# T-11_Version_1_1.net
KiCad netlist of a schematic drawn in EAGLE
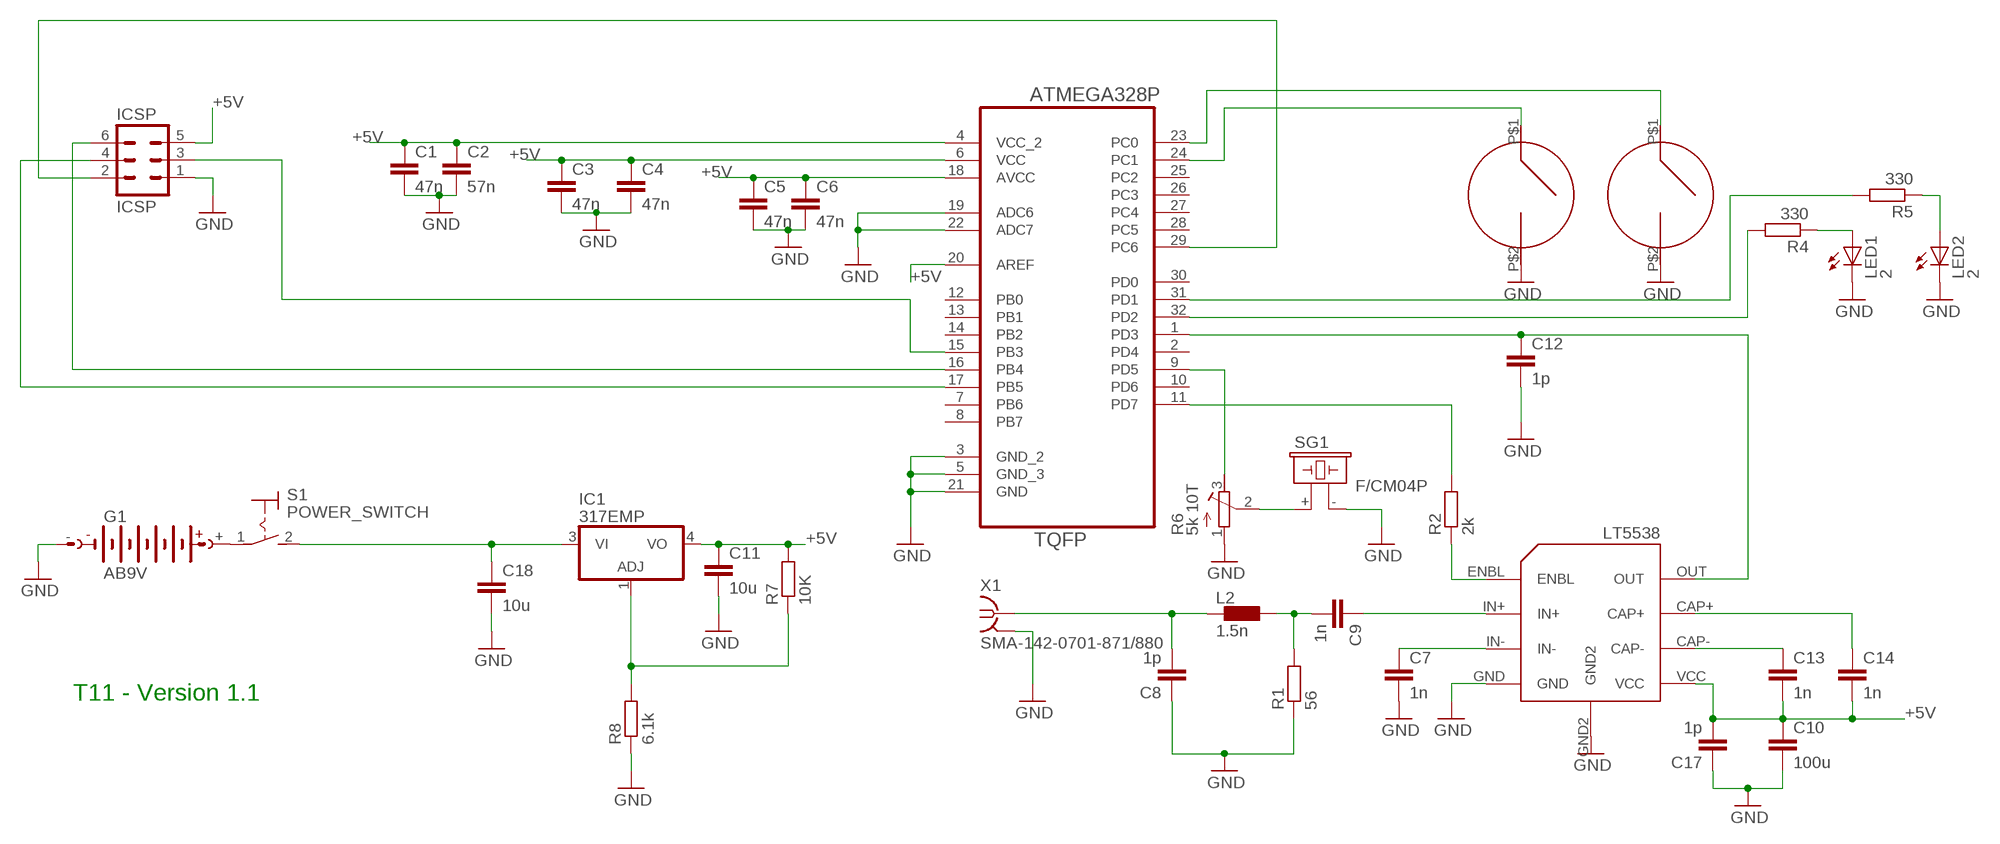
[diagram p0: schematic, sheet 1]

(export (version "E")
  (design (tool "Eeschema 10.0.6"))
  (components
    (comp (ref "C1")
      (value "47n")
      (footprint "eagle-import:C4532")
      (libsource (lib "eagle-import") (part "CC4532"))
    )
    (comp (ref "C2")
      (value "57n")
      (footprint "eagle-import:C4532")
      (libsource (lib "eagle-import") (part "CC4532"))
    )
    (comp (ref "C3")
      (value "47n")
      (footprint "eagle-import:C4532")
      (libsource (lib "eagle-import") (part "CC4532"))
    )
    (comp (ref "C4")
      (value "47n")
      (footprint "eagle-import:C4532")
      (libsource (lib "eagle-import") (part "CC4532"))
    )
    (comp (ref "C5")
      (value "47n")
      (footprint "eagle-import:C4532")
      (libsource (lib "eagle-import") (part "CC4532"))
    )
    (comp (ref "C6")
      (value "47n")
      (footprint "eagle-import:C4532")
      (libsource (lib "eagle-import") (part "CC4532"))
    )
    (comp (ref "C7")
      (value "1n")
      (footprint "eagle-import:C4532")
      (libsource (lib "eagle-import") (part "CC4532"))
    )
    (comp (ref "C8")
      (value "1p")
      (footprint "eagle-import:C4532")
      (libsource (lib "eagle-import") (part "CC4532"))
    )
    (comp (ref "C9")
      (value "1n")
      (footprint "eagle-import:C4532")
      (libsource (lib "eagle-import") (part "CC4532"))
    )
    (comp (ref "C10")
      (value "100u")
      (footprint "eagle-import:C4532")
      (libsource (lib "eagle-import") (part "CC4532"))
    )
    (comp (ref "C11")
      (value "10u")
      (footprint "eagle-import:C4532")
      (libsource (lib "eagle-import") (part "CC4532"))
    )
    (comp (ref "C12")
      (value "1p")
      (footprint "eagle-import:C0805")
      (fields (field (name "SPICEMODEL") "1p"))
      (libsource (lib "eagle-import") (part "C"))
    )
    (comp (ref "C13")
      (value "1n")
      (footprint "eagle-import:C4532")
      (libsource (lib "eagle-import") (part "CC4532"))
    )
    (comp (ref "C14")
      (value "1n")
      (footprint "eagle-import:C4532")
      (libsource (lib "eagle-import") (part "CC4532"))
    )
    (comp (ref "C17")
      (value "1p")
      (footprint "eagle-import:C4532")
      (libsource (lib "eagle-import") (part "CC4532"))
    )
    (comp (ref "C18")
      (value "10u")
      (footprint "eagle-import:C4532")
      (libsource (lib "eagle-import") (part "CC4532"))
    )
    (comp (ref "G1")
      (value "AB9V")
      (footprint "eagle-import:AB9V")
      (libsource (lib "eagle-import") (part "AB9V"))
    )
    (comp (ref "IC1")
      (value "317EMP")
      (footprint "eagle-import:SOT223")
      (libsource (lib "eagle-import") (part "317EMP"))
    )
    (comp (ref "ICSP")
      (value "ICSP")
      (footprint "eagle-import:MA03-2")
      (libsource (lib "eagle-import") (part "MA03-2"))
    )
    (comp (ref "L2")
      (value "1.5n")
      (footprint "eagle-import:L4532P")
      (libsource (lib "eagle-import") (part "LL4532P"))
    )
    (comp (ref "LED1")
      (value "2")
      (footprint "eagle-import:LED3MM")
      (libsource (lib "eagle-import") (part "LED3MM"))
    )
    (comp (ref "LED2")
      (value "2")
      (footprint "eagle-import:LED3MM")
      (libsource (lib "eagle-import") (part "LED3MM"))
    )
    (comp (ref "R1")
      (value "56")
      (footprint "eagle-import:R3225")
      (libsource (lib "eagle-import") (part "RR3225"))
    )
    (comp (ref "R2")
      (value "2k")
      (footprint "eagle-import:R3225")
      (libsource (lib "eagle-import") (part "RR3225"))
    )
    (comp (ref "R4")
      (value "330")
      (footprint "eagle-import:R3225")
      (libsource (lib "eagle-import") (part "RR3225"))
    )
    (comp (ref "R5")
      (value "330")
      (footprint "eagle-import:R3225")
      (libsource (lib "eagle-import") (part "RR3225"))
    )
    (comp (ref "R6")
      (value "5k 10T")
      (footprint "eagle-import:RTRIMTS63Y")
      (libsource (lib "eagle-import") (part "R-TRIMMTS63Y"))
    )
    (comp (ref "R7")
      (value "10K")
      (footprint "eagle-import:R3225")
      (libsource (lib "eagle-import") (part "RR3225"))
    )
    (comp (ref "R8")
      (value "6.1k")
      (footprint "eagle-import:R3225")
      (libsource (lib "eagle-import") (part "RR3225"))
    )
    (comp (ref "S1")
      (value "POWER_SWITCH")
      (footprint "eagle-import:MS243")
      (libsource (lib "eagle-import") (part "MS243"))
    )
    (comp (ref "SG1")
      (value "F/CM04P")
      (footprint "eagle-import:F_CM04P")
      (libsource (lib "eagle-import") (part "F/CM04P"))
    )
    (comp (ref "U$1")
      (value "LT5538")
      (footprint "eagle-import:LT5538")
      (libsource (lib "eagle-import") (part "LT5538"))
    )
    (comp (ref "U$2")
      (value "SW-1801X")
      (footprint "eagle-import:SW-1801X")
      (libsource (lib "eagle-import") (part "SW-1801X"))
    )
    (comp (ref "U$3")
      (value "SW-1801X")
      (footprint "eagle-import:SW-1801X")
      (libsource (lib "eagle-import") (part "SW-1801X"))
    )
    (comp (ref "U1")
      (value "ATMEGA328P-AU")
      (footprint "eagle-import:QFP80P900X900X120-32N")
      (libsource (lib "eagle-import") (part "ATMEGA328P-AU"))
    )
    (comp (ref "X1")
      (value "SMA-142-0701-871/880")
      (footprint "eagle-import:SMA-142-0701-871")
      (fields (field (name "MF") "JOHNSON COMPONENTS") (field (name "MPN") "142-0701-871"))
      (libsource (lib "eagle-import") (part "SMA-142-0701-871/880"))
    )
  )
  (nets
    (net (code "1") (name "/+5V") (class "Default")
      (node (ref "C1") (pin "1") (pinfunction "1_1") (pintype "passive"))
      (node (ref "C10") (pin "1") (pinfunction "1_1") (pintype "passive"))
      (node (ref "C11") (pin "1") (pinfunction "1_1") (pintype "passive"))
      (node (ref "C13") (pin "2") (pinfunction "2_2") (pintype "passive"))
      (node (ref "C14") (pin "2") (pinfunction "2_2") (pintype "passive"))
      (node (ref "C17") (pin "2") (pinfunction "2_2") (pintype "passive"))
      (node (ref "C2") (pin "1") (pinfunction "1_1") (pintype "passive"))
      (node (ref "C3") (pin "1") (pinfunction "1_1") (pintype "passive"))
      (node (ref "C4") (pin "1") (pinfunction "1_1") (pintype "passive"))
      (node (ref "C5") (pin "1") (pinfunction "1_1") (pintype "passive"))
      (node (ref "C6") (pin "1") (pinfunction "1_1") (pintype "passive"))
      (node (ref "IC1") (pin "4") (pinfunction "VO_4") (pintype "passive"))
      (node (ref "ICSP") (pin "5") (pinfunction "5_5") (pintype "passive"))
      (node (ref "R7") (pin "2") (pinfunction "2_2") (pintype "passive"))
      (node (ref "U$1") (pin "VCC") (pinfunction "VCC_VCC") (pintype "power_in"))
      (node (ref "U1") (pin "18") (pinfunction "AVCC_18") (pintype "power_in"))
      (node (ref "U1") (pin "20") (pinfunction "AREF_20") (pintype "input"))
      (node (ref "U1") (pin "4") (pinfunction "VCC_2_4") (pintype "power_in"))
      (node (ref "U1") (pin "6") (pinfunction "VCC_6") (pintype "power_in"))
    )
    (net (code "2") (name "GND") (class "Default")
      (node (ref "C1") (pin "2") (pinfunction "2_2") (pintype "passive"))
      (node (ref "C10") (pin "2") (pinfunction "2_2") (pintype "passive"))
      (node (ref "C11") (pin "2") (pinfunction "2_2") (pintype "passive"))
      (node (ref "C12") (pin "2") (pinfunction "2_2") (pintype "passive"))
      (node (ref "C17") (pin "1") (pinfunction "1_1") (pintype "passive"))
      (node (ref "C18") (pin "2") (pinfunction "2_2") (pintype "passive"))
      (node (ref "C2") (pin "2") (pinfunction "2_2") (pintype "passive"))
      (node (ref "C3") (pin "2") (pinfunction "2_2") (pintype "passive"))
      (node (ref "C4") (pin "2") (pinfunction "2_2") (pintype "passive"))
      (node (ref "C5") (pin "2") (pinfunction "2_2") (pintype "passive"))
      (node (ref "C6") (pin "2") (pinfunction "2_2") (pintype "passive"))
      (node (ref "C7") (pin "2") (pinfunction "2_2") (pintype "passive"))
      (node (ref "C8") (pin "1") (pinfunction "1_1") (pintype "passive"))
      (node (ref "G1") (pin "-") (pinfunction "-_-") (pintype "passive"))
      (node (ref "ICSP") (pin "1") (pinfunction "1_1") (pintype "passive"))
      (node (ref "LED1") (pin "K") (pinfunction "C_K") (pintype "passive"))
      (node (ref "LED2") (pin "K") (pinfunction "C_K") (pintype "passive"))
      (node (ref "R1") (pin "1") (pinfunction "1_1") (pintype "passive"))
      (node (ref "R6") (pin "1") (pinfunction "A_1") (pintype "passive"))
      (node (ref "R8") (pin "1") (pinfunction "1_1") (pintype "passive"))
      (node (ref "SG1") (pin "-") (pinfunction "2_-") (pintype "passive"))
      (node (ref "U$1") (pin "GND") (pinfunction "GND_GND") (pintype "power_in"))
      (node (ref "U$1") (pin "GND2") (pinfunction "GND2_GND2") (pintype "bidirectional"))
      (node (ref "U$2") (pin "P$2") (pinfunction "P$2_P$2") (pintype "bidirectional"))
      (node (ref "U$3") (pin "P$2") (pinfunction "P$2_P$2") (pintype "bidirectional"))
      (node (ref "U1") (pin "19") (pinfunction "ADC6_19") (pintype "input"))
      (node (ref "U1") (pin "21") (pinfunction "GND_21") (pintype "passive"))
      (node (ref "U1") (pin "22") (pinfunction "ADC7_22") (pintype "input"))
      (node (ref "U1") (pin "3") (pinfunction "GND_2_3") (pintype "passive"))
      (node (ref "U1") (pin "5") (pinfunction "GND_3_5") (pintype "passive"))
      (node (ref "X1") (pin "2@1") (pinfunction "2_2@1") (pintype "passive"))
      (node (ref "X1") (pin "2@2") (pinfunction "2_2@2") (pintype "passive"))
      (node (ref "X1") (pin "2@3") (pinfunction "2_2@3") (pintype "passive"))
      (node (ref "X1") (pin "2@4") (pinfunction "2_2@4") (pintype "passive"))
    )
    (net (code "3") (name "Net-(C7-Pad1)") (class "Default")
      (node (ref "C7") (pin "1") (pinfunction "1_1") (pintype "passive"))
      (node (ref "U$1") (pin "IN-") (pinfunction "IN-_IN-") (pintype "bidirectional"))
    )
    (net (code "4") (name "Net-(C8-Pad2)") (class "Default")
      (node (ref "C8") (pin "2") (pinfunction "2_2") (pintype "passive"))
      (node (ref "L2") (pin "2") (pinfunction "2_2") (pintype "passive"))
      (node (ref "X1") (pin "1") (pinfunction "1_1") (pintype "passive"))
    )
    (net (code "5") (name "Net-(C9-Pad1)") (class "Default")
      (node (ref "C9") (pin "1") (pinfunction "1_1") (pintype "passive"))
      (node (ref "U$1") (pin "IN+") (pinfunction "IN+_IN+") (pintype "bidirectional"))
    )
    (net (code "6") (name "Net-(C9-Pad2)") (class "Default")
      (node (ref "C9") (pin "2") (pinfunction "2_2") (pintype "passive"))
      (node (ref "L2") (pin "1") (pinfunction "1_1") (pintype "passive"))
      (node (ref "R1") (pin "2") (pinfunction "2_2") (pintype "passive"))
    )
    (net (code "7") (name "Net-(C13-Pad1)") (class "Default")
      (node (ref "C13") (pin "1") (pinfunction "1_1") (pintype "passive"))
      (node (ref "U$1") (pin "CAP-") (pinfunction "CAP-_CAP-") (pintype "bidirectional"))
    )
    (net (code "8") (name "Net-(C14-Pad1)") (class "Default")
      (node (ref "C14") (pin "1") (pinfunction "1_1") (pintype "passive"))
      (node (ref "U$1") (pin "CAP+") (pinfunction "CAP+_CAP+") (pintype "bidirectional"))
    )
    (net (code "9") (name "Net-(IC1-ADJ)") (class "Default")
      (node (ref "IC1") (pin "1") (pinfunction "ADJ_1") (pintype "input"))
      (node (ref "R7") (pin "1") (pinfunction "1_1") (pintype "passive"))
      (node (ref "R8") (pin "2") (pinfunction "2_2") (pintype "passive"))
    )
    (net (code "10") (name "Net-(IC1-VI)") (class "Default")
      (node (ref "C18") (pin "1") (pinfunction "1_1") (pintype "passive"))
      (node (ref "IC1") (pin "3") (pinfunction "VI_3") (pintype "input"))
      (node (ref "S1") (pin "2") (pinfunction "S_2") (pintype "passive"))
    )
    (net (code "11") (name "Net-(LED1-PadA)") (class "Default")
      (node (ref "LED1") (pin "A") (pinfunction "A_A") (pintype "passive"))
      (node (ref "R4") (pin "1") (pinfunction "1_1") (pintype "passive"))
    )
    (net (code "12") (name "Net-(LED2-PadA)") (class "Default")
      (node (ref "LED2") (pin "A") (pinfunction "A_A") (pintype "passive"))
      (node (ref "R5") (pin "1") (pinfunction "1_1") (pintype "passive"))
    )
    (net (code "13") (name "Net-(R2-Pad1)") (class "Default")
      (node (ref "R2") (pin "1") (pinfunction "1_1") (pintype "passive"))
      (node (ref "U$1") (pin "ENBL") (pinfunction "ENBL_ENBL") (pintype "bidirectional"))
    )
    (net (code "14") (name "Net-(R6-E)") (class "Default")
      (node (ref "R6") (pin "3") (pinfunction "E_3") (pintype "passive"))
      (node (ref "U1") (pin "9") (pinfunction "PD5_9") (pintype "bidirectional"))
    )
    (net (code "15") (name "Net-(R6-S)") (class "Default")
      (node (ref "R6") (pin "2") (pinfunction "S_2") (pintype "passive"))
      (node (ref "SG1") (pin "+") (pinfunction "1_+") (pintype "passive"))
    )
    (net (code "16") (name "Net-(S1-P)") (class "Default")
      (node (ref "G1") (pin "+") (pinfunction "+_+") (pintype "passive"))
      (node (ref "S1") (pin "1") (pinfunction "P_1") (pintype "passive"))
    )
    (net (code "17") (name "Net-(U1-PB3)") (class "Default")
      (node (ref "ICSP") (pin "3") (pinfunction "3_3") (pintype "passive"))
      (node (ref "U1") (pin "15") (pinfunction "PB3_15") (pintype "bidirectional"))
    )
    (net (code "18") (name "Net-(U1-PB4)") (class "Default")
      (node (ref "ICSP") (pin "6") (pinfunction "6_6") (pintype "passive"))
      (node (ref "U1") (pin "16") (pinfunction "PB4_16") (pintype "bidirectional"))
    )
    (net (code "19") (name "Net-(U1-PB5)") (class "Default")
      (node (ref "ICSP") (pin "4") (pinfunction "4_4") (pintype "passive"))
      (node (ref "U1") (pin "17") (pinfunction "PB5_17") (pintype "bidirectional"))
    )
    (net (code "20") (name "Net-(U1-PC0)") (class "Default")
      (node (ref "U$2") (pin "P$1") (pinfunction "P$1_P$1") (pintype "bidirectional"))
      (node (ref "U1") (pin "23") (pinfunction "PC0_23") (pintype "bidirectional"))
    )
    (net (code "21") (name "Net-(U1-PC1)") (class "Default")
      (node (ref "U$3") (pin "P$1") (pinfunction "P$1_P$1") (pintype "bidirectional"))
      (node (ref "U1") (pin "24") (pinfunction "PC1_24") (pintype "bidirectional"))
    )
    (net (code "22") (name "Net-(U1-PC6)") (class "Default")
      (node (ref "ICSP") (pin "2") (pinfunction "2_2") (pintype "passive"))
      (node (ref "U1") (pin "29") (pinfunction "PC6_29") (pintype "bidirectional"))
    )
    (net (code "23") (name "Net-(U1-PD1)") (class "Default")
      (node (ref "R5") (pin "2") (pinfunction "2_2") (pintype "passive"))
      (node (ref "U1") (pin "31") (pinfunction "PD1_31") (pintype "bidirectional"))
    )
    (net (code "24") (name "Net-(U1-PD2)") (class "Default")
      (node (ref "R4") (pin "2") (pinfunction "2_2") (pintype "passive"))
      (node (ref "U1") (pin "32") (pinfunction "PD2_32") (pintype "bidirectional"))
    )
    (net (code "25") (name "Net-(U1-PD3)") (class "Default")
      (node (ref "C12") (pin "1") (pinfunction "1_1") (pintype "passive"))
      (node (ref "U$1") (pin "OUT") (pinfunction "OUT_OUT") (pintype "output"))
      (node (ref "U1") (pin "1") (pinfunction "PD3_1") (pintype "bidirectional"))
    )
    (net (code "26") (name "Net-(U1-PD7)") (class "Default")
      (node (ref "R2") (pin "2") (pinfunction "2_2") (pintype "passive"))
      (node (ref "U1") (pin "11") (pinfunction "PD7_11") (pintype "bidirectional"))
    )
    (net (code "27") (name "unconnected-(U1-PB0-Pad12)") (class "Default")
      (node (ref "U1") (pin "12") (pinfunction "PB0_12") (pintype "bidirectional"))
    )
    (net (code "28") (name "unconnected-(U1-PB1-Pad13)") (class "Default")
      (node (ref "U1") (pin "13") (pinfunction "PB1_13") (pintype "bidirectional"))
    )
    (net (code "29") (name "unconnected-(U1-PB2-Pad14)") (class "Default")
      (node (ref "U1") (pin "14") (pinfunction "PB2_14") (pintype "bidirectional"))
    )
    (net (code "30") (name "unconnected-(U1-PB6-Pad7)") (class "Default")
      (node (ref "U1") (pin "7") (pinfunction "PB6_7") (pintype "bidirectional"))
    )
    (net (code "31") (name "unconnected-(U1-PB7-Pad8)") (class "Default")
      (node (ref "U1") (pin "8") (pinfunction "PB7_8") (pintype "bidirectional"))
    )
    (net (code "32") (name "unconnected-(U1-PC2-Pad25)") (class "Default")
      (node (ref "U1") (pin "25") (pinfunction "PC2_25") (pintype "bidirectional"))
    )
    (net (code "33") (name "unconnected-(U1-PC3-Pad26)") (class "Default")
      (node (ref "U1") (pin "26") (pinfunction "PC3_26") (pintype "bidirectional"))
    )
    (net (code "34") (name "unconnected-(U1-PC4-Pad27)") (class "Default")
      (node (ref "U1") (pin "27") (pinfunction "PC4_27") (pintype "bidirectional"))
    )
    (net (code "35") (name "unconnected-(U1-PC5-Pad28)") (class "Default")
      (node (ref "U1") (pin "28") (pinfunction "PC5_28") (pintype "bidirectional"))
    )
    (net (code "36") (name "unconnected-(U1-PD0-Pad30)") (class "Default")
      (node (ref "U1") (pin "30") (pinfunction "PD0_30") (pintype "bidirectional"))
    )
    (net (code "37") (name "unconnected-(U1-PD4-Pad2)") (class "Default")
      (node (ref "U1") (pin "2") (pinfunction "PD4_2") (pintype "bidirectional"))
    )
    (net (code "38") (name "unconnected-(U1-PD6-Pad10)") (class "Default")
      (node (ref "U1") (pin "10") (pinfunction "PD6_10") (pintype "bidirectional"))
    )
  )
)
